# uMultimeter_ExpIO_Sch.net
KiCad netlist of a schematic drawn in Altium Designer
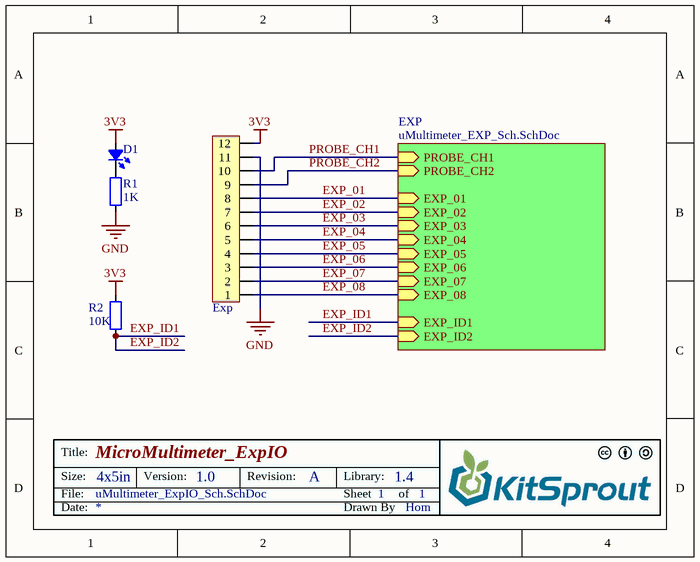
[diagram p0: uMultimeter_ExpIO_Sch.SchDoc]

(export (version "E")
  (design (tool "Eeschema 10.0.6"))
  (components
    (comp (ref "D1")
      (value "LED_0805")
      (footprint "PCB_ActiveLED:LED_0805_BLUE")
      (description "LED")
      (libsource (lib "SCH_Active") (part "LED_0805"))
    )
    (comp (ref "Exp")
      (value "HDR1x12_2.54")
      (footprint "PCB_ConnectorHDR:HDR1X12_2.54_180H")
      (description "Header")
      (libsource (lib "SCH_ConnectorHDR") (part "HDR1x12_2.54"))
    )
    (comp (ref "R1")
      (value "1K")
      (footprint "PCB_PassiveRes:RES_0603")
      (description "Resistor")
      (fields (field (name "Comment") "Res_0603"))
      (libsource (lib "SCH_Passive") (part "Res_0603"))
    )
    (comp (ref "R2")
      (value "10K")
      (footprint "PCB_PassiveRes:RES_0603")
      (description "Resistor")
      (fields (field (name "Comment") "Res_0603"))
      (libsource (lib "SCH_Passive") (part "Res_0603"))
    )
  )
  (nets
    (net (code "1") (name "/EXP_01") (class "Default")
      (node (ref "Exp") (pin "8") (pinfunction "8_8") (pintype "passive"))
    )
    (net (code "2") (name "/EXP_02") (class "Default")
      (node (ref "Exp") (pin "7") (pinfunction "7_7") (pintype "passive"))
    )
    (net (code "3") (name "/EXP_03") (class "Default")
      (node (ref "Exp") (pin "6") (pinfunction "6_6") (pintype "passive"))
    )
    (net (code "4") (name "/EXP_04") (class "Default")
      (node (ref "Exp") (pin "5") (pinfunction "5_5") (pintype "passive"))
    )
    (net (code "5") (name "/EXP_05") (class "Default")
      (node (ref "Exp") (pin "4") (pinfunction "4_4") (pintype "passive"))
    )
    (net (code "6") (name "/EXP_06") (class "Default")
      (node (ref "Exp") (pin "3") (pinfunction "3_3") (pintype "passive"))
    )
    (net (code "7") (name "/EXP_07") (class "Default")
      (node (ref "Exp") (pin "2") (pinfunction "2_2") (pintype "passive"))
    )
    (net (code "8") (name "/EXP_08") (class "Default")
      (node (ref "Exp") (pin "1") (pinfunction "1_1") (pintype "passive"))
    )
    (net (code "9") (name "/EXP_ID1") (class "Default")
      (node (ref "R2") (pin "2") (pinfunction "2_2") (pintype "passive"))
    )
    (net (code "10") (name "/PROBE_CH1") (class "Default")
      (node (ref "Exp") (pin "10") (pinfunction "10_10") (pintype "passive"))
    )
    (net (code "11") (name "/PROBE_CH2") (class "Default")
      (node (ref "Exp") (pin "9") (pinfunction "9_9") (pintype "passive"))
    )
    (net (code "12") (name "3V3") (class "Default")
      (node (ref "D1") (pin "1") (pinfunction "A_1") (pintype "passive"))
      (node (ref "Exp") (pin "12") (pinfunction "12_12") (pintype "passive"))
      (node (ref "R2") (pin "1") (pinfunction "1_1") (pintype "passive"))
    )
    (net (code "13") (name "GND") (class "Default")
      (node (ref "Exp") (pin "11") (pinfunction "11_11") (pintype "passive"))
      (node (ref "R1") (pin "2") (pinfunction "2_2") (pintype "passive"))
    )
    (net (code "14") (name "Net-(D1-K)") (class "Default")
      (node (ref "D1") (pin "2") (pinfunction "K_2") (pintype "passive"))
      (node (ref "R1") (pin "1") (pinfunction "1_1") (pintype "passive"))
    )
  )
)
